# DSR-0609-ES8218-0410.net
KiCad netlist of a schematic drawn in Altium Designer
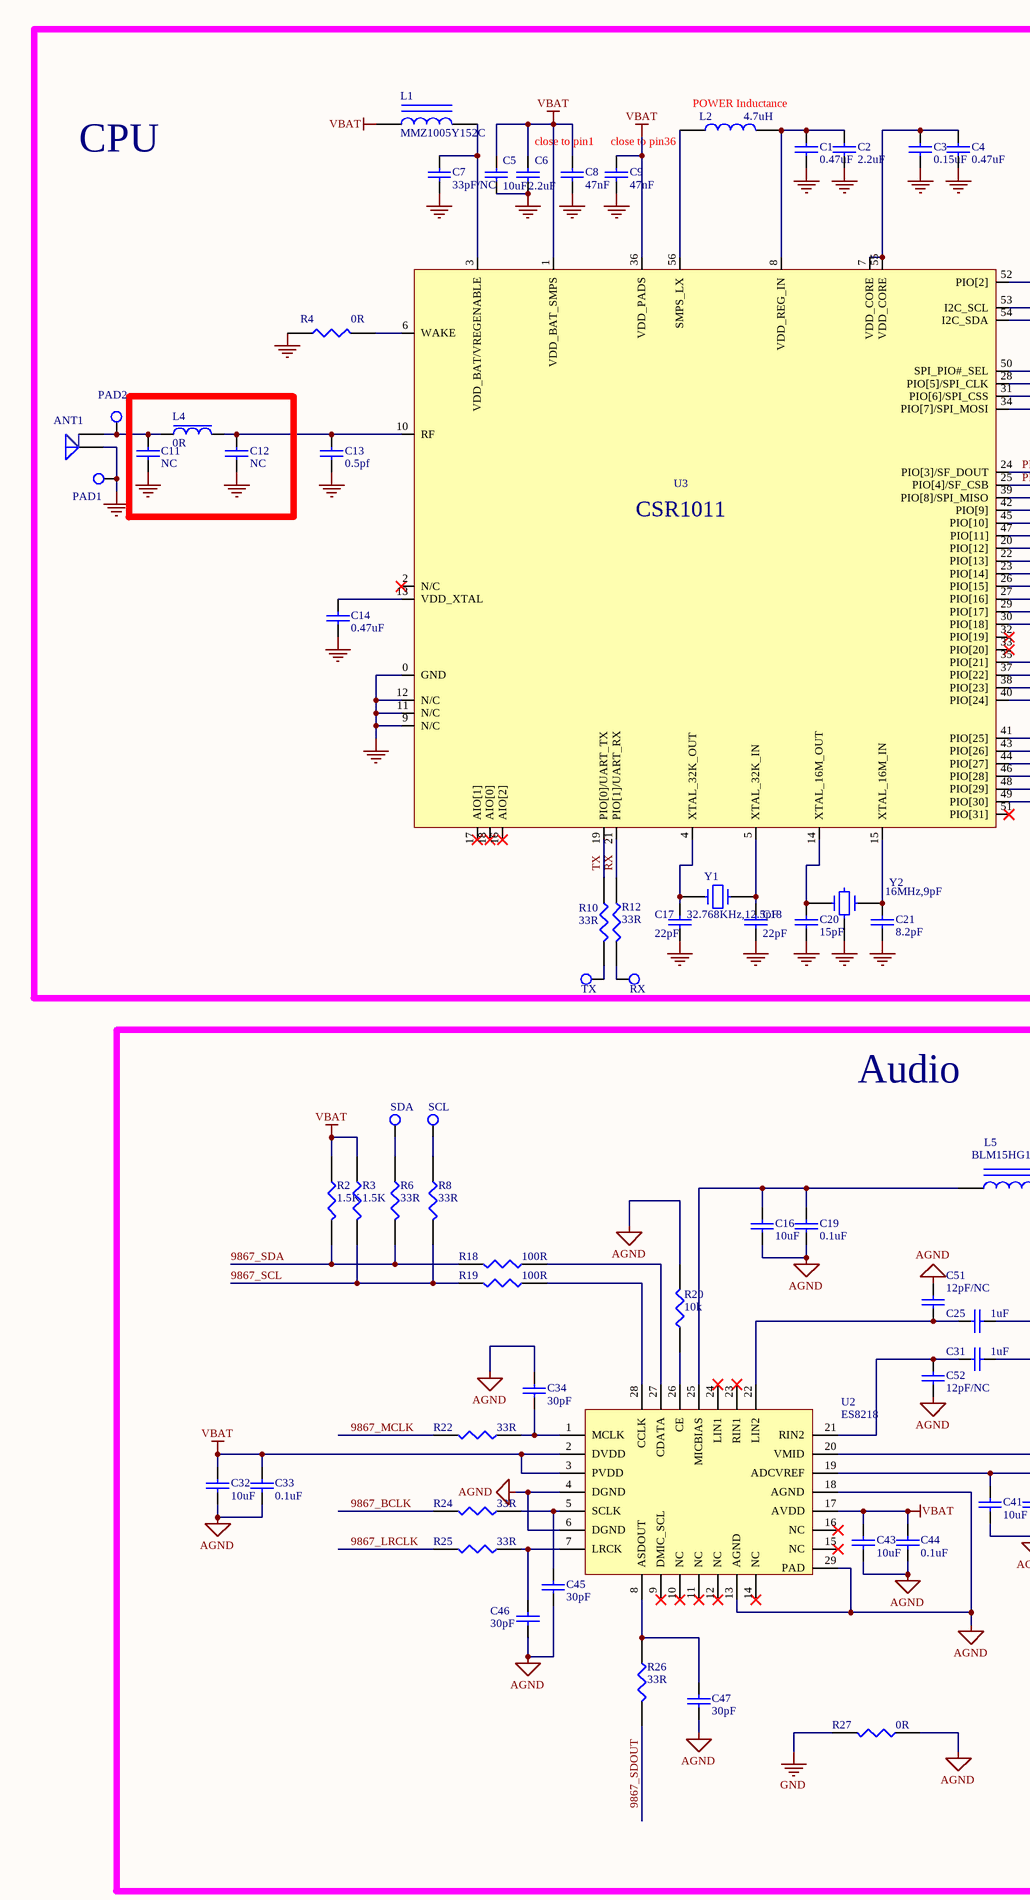
[diagram p0: DSR-0609-ES8218-0410.SchDoc, left]
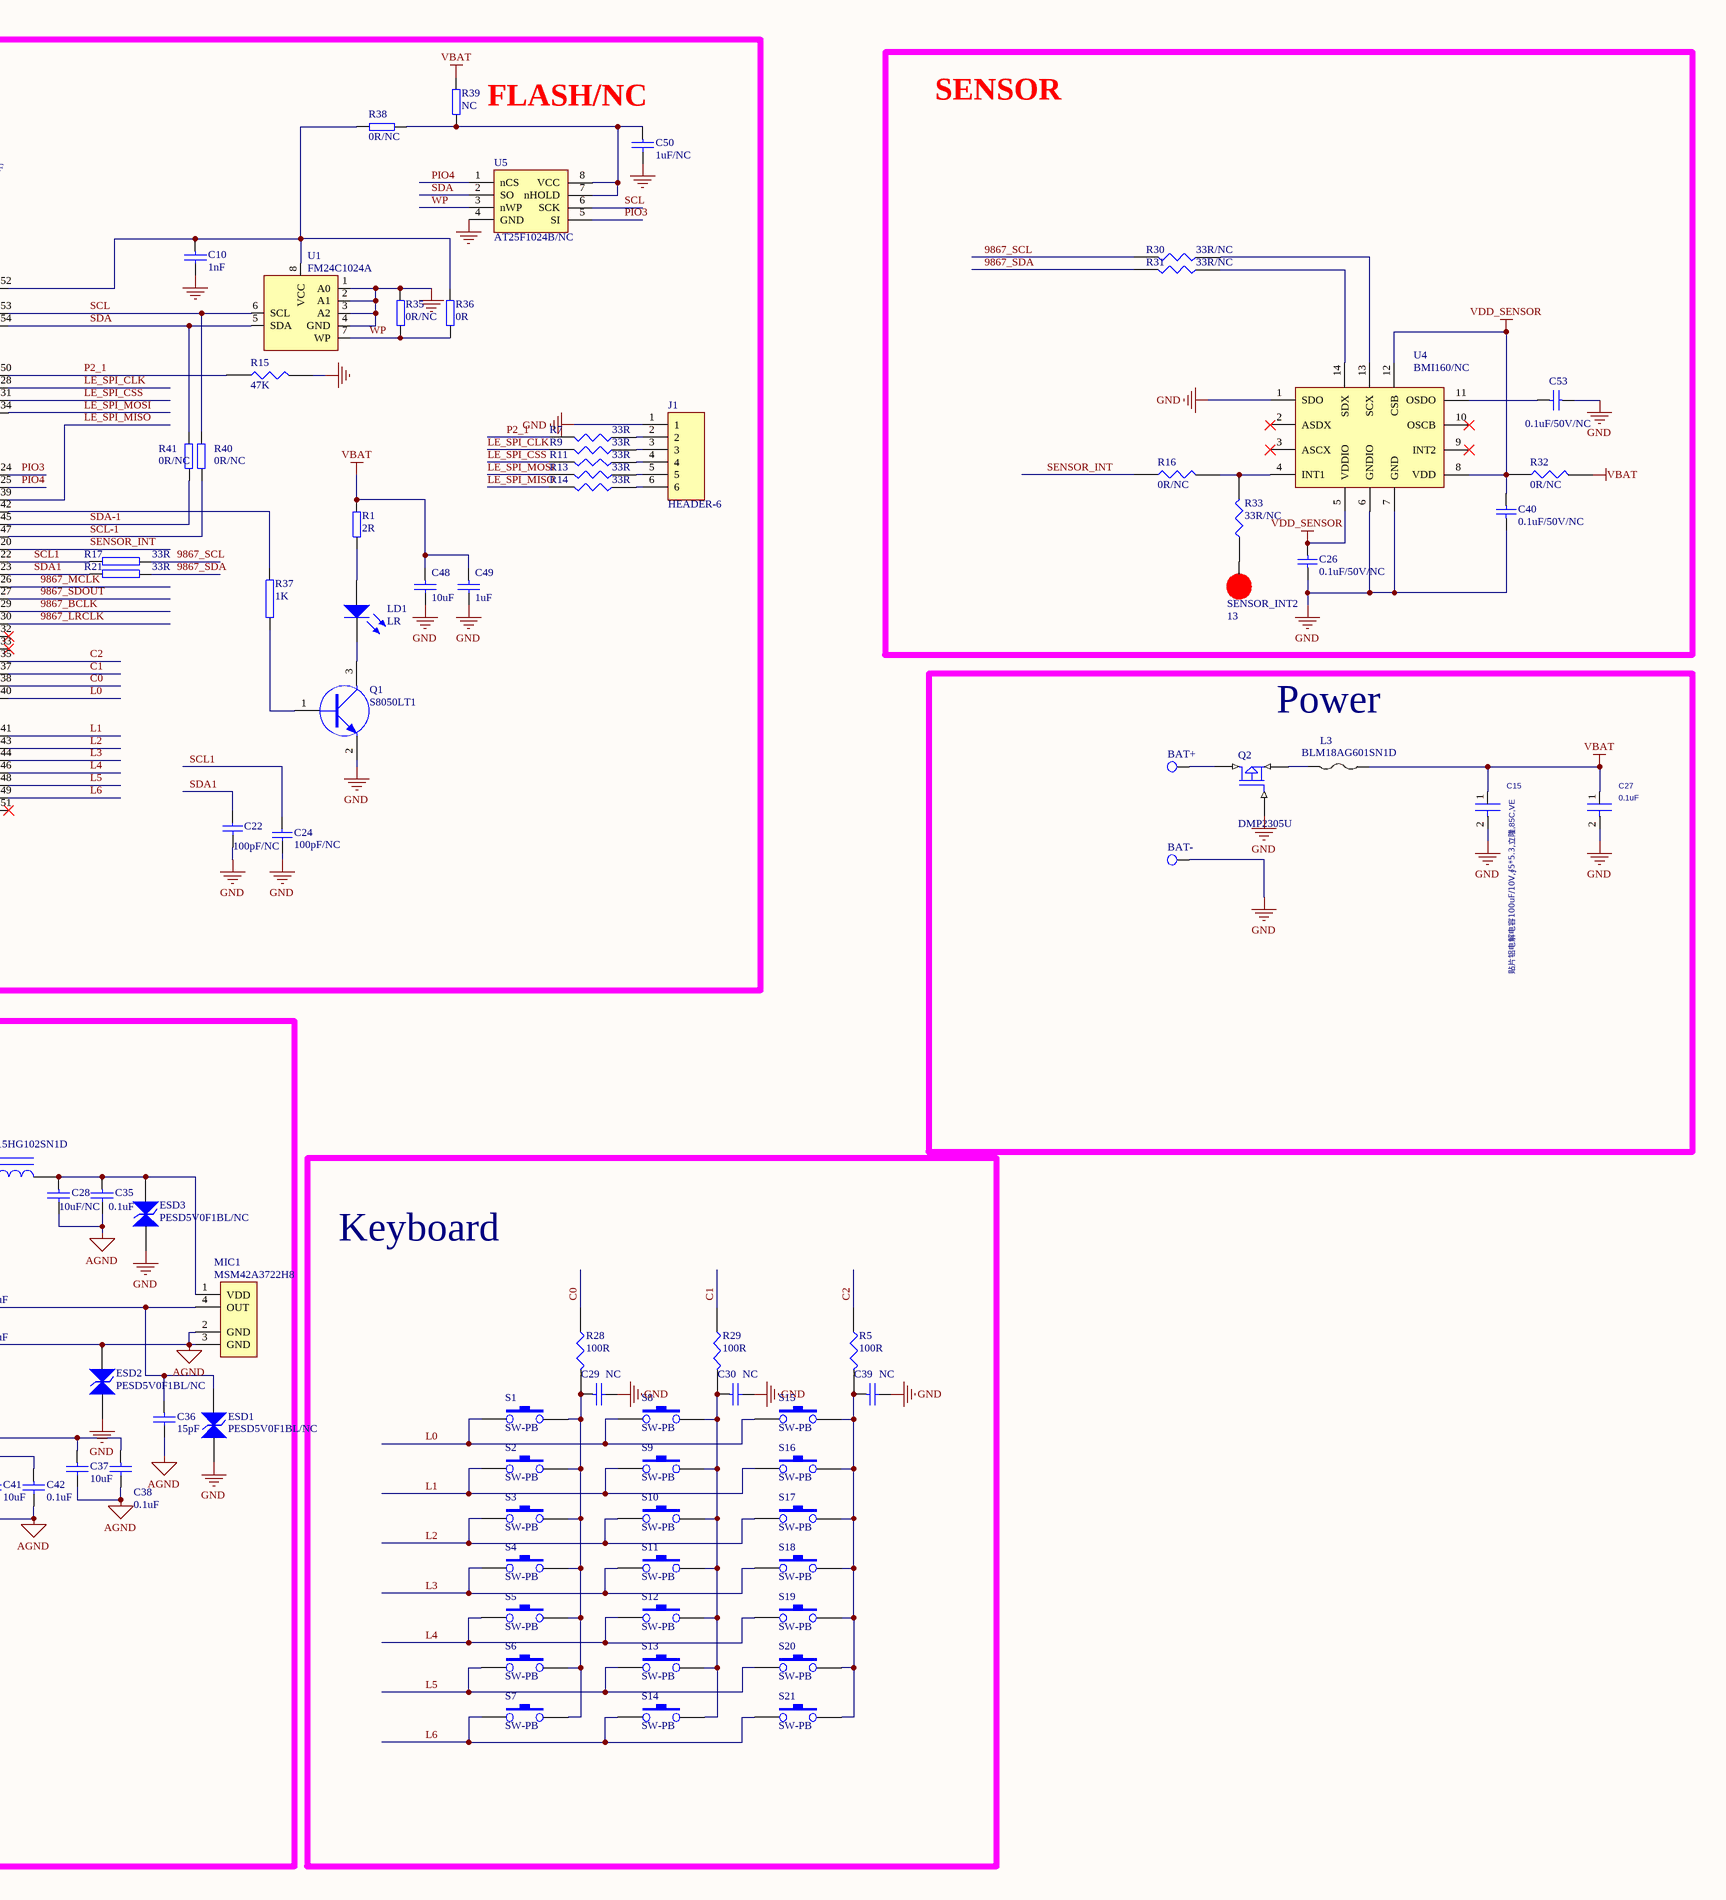
[diagram p1: DSR-0609-ES8218-0410.SchDoc, right]

(export (version "E")
  (design (tool "Eeschema 10.0.6"))
  (components
    (comp (ref "ANT1")
      (value "ANTENNA")
      (footprint "ACA-2012-A1-CC-S")
      (libsource (lib "dusun01-SCH") (part "ANTENNA"))
    )
    (comp (ref "BAT+") (value "TAP") (footprint "BAT") (libsource (lib "*") (part "TAP")))
    (comp (ref "BAT-") (value "TAP") (footprint "BAT") (libsource (lib "*") (part "TAP")))
    (comp (ref "C1")
      (value "0.47uF")
      (footprint "dusun01-pcb:C-0402")
      (description "Capacitor")
      (libsource (lib "*") (part "CAP"))
    )
    (comp (ref "C2")
      (value "2.2uF")
      (footprint "dusun01-pcb:C-0402")
      (description "Capacitor")
      (libsource (lib "*") (part "CAP"))
    )
    (comp (ref "C3")
      (value "0.15uF")
      (footprint "dusun01-pcb:C-0402")
      (description "Capacitor")
      (libsource (lib "*") (part "CAP"))
    )
    (comp (ref "C4")
      (value "0.47uF")
      (footprint "dusun01-pcb:C-0402")
      (description "Capacitor")
      (libsource (lib "*") (part "CAP"))
    )
    (comp (ref "C5")
      (value "10uF")
      (footprint "dusun01-pcb:C-0603")
      (description "Capacitor")
      (libsource (lib "*") (part "CAP"))
    )
    (comp (ref "C6")
      (value "2.2uF")
      (footprint "dusun01-pcb:C-0402")
      (description "Capacitor")
      (libsource (lib "*") (part "CAP"))
    )
    (comp (ref "C7")
      (value "33pF/NC")
      (footprint "dusun01-pcb:C-0402")
      (description "Capacitor")
      (libsource (lib "*") (part "CAP"))
    )
    (comp (ref "C8")
      (value "47nF")
      (footprint "dusun01-pcb:C-0402")
      (description "Capacitor")
      (libsource (lib "*") (part "CAP"))
    )
    (comp (ref "C9")
      (value "47nF")
      (footprint "dusun01-pcb:C-0402")
      (description "Capacitor")
      (libsource (lib "*") (part "CAP"))
    )
    (comp (ref "C10")
      (value "1nF")
      (footprint "dusun01-pcb:C-0402")
      (description "Capacitor")
      (libsource (lib "*") (part "CAP"))
    )
    (comp (ref "C11")
      (value "NC")
      (footprint "dusun01-pcb:C-0402")
      (description "Capacitor")
      (libsource (lib "*") (part "CAP"))
    )
    (comp (ref "C12")
      (value "NC")
      (footprint "dusun01-pcb:C-0402")
      (description "Capacitor")
      (libsource (lib "*") (part "CAP"))
    )
    (comp (ref "C13")
      (value "0.5pf")
      (footprint "dusun01-pcb:C-0402")
      (description "Capacitor")
      (libsource (lib "*") (part "CAP"))
    )
    (comp (ref "C14")
      (value "0.47uF")
      (footprint "dusun01-pcb:C-0402")
      (description "Capacitor")
      (libsource (lib "*") (part "CAP"))
    )
    (comp (ref "C15")
      (value "贴片铝电解电容100uF/10V,∮5*5.3,立隆,85C,VE")
      (footprint "dusun02-pcb:CAP_ALUM-C")
      (libsource (lib "*") (part "C_Dup1"))
    )
    (comp (ref "C16")
      (value "10uF")
      (footprint "dusun01-pcb:C-0603")
      (description "Capacitor")
      (libsource (lib "*") (part "CAP"))
    )
    (comp (ref "C17")
      (value "22pF")
      (footprint "dusun01-pcb:C-0402")
      (description "Capacitor")
      (libsource (lib "*") (part "CAP"))
    )
    (comp (ref "C18")
      (value "22pF")
      (footprint "dusun01-pcb:C-0402")
      (description "Capacitor")
      (libsource (lib "*") (part "CAP"))
    )
    (comp (ref "C19")
      (value "0.1uF")
      (footprint "C-0402")
      (description "Capacitor")
      (libsource (lib "*") (part "CAP"))
    )
    (comp (ref "C20")
      (value "15pF")
      (footprint "dusun01-pcb:C-0402")
      (description "Capacitor")
      (libsource (lib "*") (part "CAP"))
    )
    (comp (ref "C21")
      (value "8.2pF")
      (footprint "dusun01-pcb:C-0402")
      (description "Capacitor")
      (libsource (lib "*") (part "CAP"))
    )
    (comp (ref "C22") (value "100pF/NC") (footprint "dusun01-pcb:C-0402") (libsource (lib "") (part "CAP_1")))
    (comp (ref "C24") (value "100pF/NC") (footprint "dusun01-pcb:C-0402") (libsource (lib "") (part "CAP_1")))
    (comp (ref "C25")
      (value "1uF")
      (footprint "C-0402")
      (description "Capacitor")
      (libsource (lib "*") (part "CAP"))
    )
    (comp (ref "C26")
      (value "0.1uF/50V/NC")
      (footprint "C-0402")
      (description "capacitor 27 pF NPO , +/- 2 %, SMD case 0603")
      (fields
        (field (name "MANUFACTURER") "Generic Components")
        (field (name "PUBLISHER") "Altium Hobart Technology Centre")
      )
      (libsource (lib "Miscellaneous Devices") (part "Cap"))
    )
    (comp (ref "C27") (value "0.1uF") (footprint "C-0603") (libsource (lib "*") (part "C_Dup1")))
    (comp (ref "C28")
      (value "10uF/NC")
      (footprint "dusun01-pcb:C-0603")
      (description "Capacitor")
      (libsource (lib "*") (part "CAP"))
    )
    (comp (ref "C29")
      (value "NC")
      (footprint "C-0402")
      (description "Capacitor")
      (libsource (lib "*") (part "CAP"))
    )
    (comp (ref "C30")
      (value "NC")
      (footprint "C-0402")
      (description "Capacitor")
      (libsource (lib "*") (part "CAP"))
    )
    (comp (ref "C31")
      (value "1uF")
      (footprint "C-0402")
      (description "Capacitor")
      (libsource (lib "*") (part "CAP"))
    )
    (comp (ref "C32")
      (value "10uF")
      (footprint "dusun01-pcb:C-0603")
      (description "Capacitor")
      (libsource (lib "*") (part "CAP"))
    )
    (comp (ref "C33")
      (value "0.1uF")
      (footprint "C-0402")
      (description "Capacitor")
      (libsource (lib "*") (part "CAP"))
    )
    (comp (ref "C34")
      (value "30pF")
      (footprint "C-0402")
      (description "Capacitor")
      (libsource (lib "*") (part "CAP"))
    )
    (comp (ref "C35")
      (value "0.1uF")
      (footprint "C-0402")
      (description "Capacitor")
      (libsource (lib "*") (part "CAP"))
    )
    (comp (ref "C36")
      (value "15pF")
      (footprint "dusun01-pcb:C-0402")
      (description "Capacitor")
      (libsource (lib "*") (part "CAP"))
    )
    (comp (ref "C37")
      (value "10uF")
      (footprint "dusun01-pcb:C-0603")
      (description "Capacitor")
      (libsource (lib "*") (part "CAP"))
    )
    (comp (ref "C38")
      (value "0.1uF")
      (footprint "C-0402")
      (description "Capacitor")
      (libsource (lib "*") (part "CAP"))
    )
    (comp (ref "C39")
      (value "NC")
      (footprint "C-0402")
      (description "Capacitor")
      (libsource (lib "*") (part "CAP"))
    )
    (comp (ref "C40")
      (value "0.1uF/50V/NC")
      (footprint "C-0402")
      (description "capacitor 27 pF NPO , +/- 2 %, SMD case 0603")
      (fields
        (field (name "MANUFACTURER") "Generic Components")
        (field (name "PUBLISHER") "Altium Hobart Technology Centre")
      )
      (libsource (lib "Miscellaneous Devices") (part "Cap"))
    )
    (comp (ref "C41")
      (value "10uF")
      (footprint "dusun01-pcb:C-0603")
      (description "Capacitor")
      (libsource (lib "*") (part "CAP"))
    )
    (comp (ref "C42")
      (value "0.1uF")
      (footprint "C-0402")
      (description "Capacitor")
      (libsource (lib "*") (part "CAP"))
    )
    (comp (ref "C43")
      (value "10uF")
      (footprint "dusun01-pcb:C-0603")
      (description "Capacitor")
      (libsource (lib "*") (part "CAP"))
    )
    (comp (ref "C44")
      (value "0.1uF")
      (footprint "C-0402")
      (description "Capacitor")
      (libsource (lib "*") (part "CAP"))
    )
    (comp (ref "C45")
      (value "30pF")
      (footprint "C-0402")
      (description "Capacitor")
      (libsource (lib "*") (part "CAP"))
    )
    (comp (ref "C46")
      (value "30pF")
      (footprint "C-0402")
      (description "Capacitor")
      (libsource (lib "*") (part "CAP"))
    )
    (comp (ref "C47")
      (value "30pF")
      (footprint "C-0402")
      (description "Capacitor")
      (libsource (lib "*") (part "CAP"))
    )
    (comp (ref "C48")
      (value "10uF")
      (footprint "dusun01-pcb:C-0603")
      (description "Capacitor")
      (libsource (lib "*") (part "CAP"))
    )
    (comp (ref "C49")
      (value "1uF")
      (footprint "dusun01-pcb:C-0603")
      (description "Capacitor")
      (libsource (lib "*") (part "CAP"))
    )
    (comp (ref "C50")
      (value "1uF/NC")
      (footprint "C-0402")
      (description "Capacitor")
      (libsource (lib "") (part "CAP_2"))
    )
    (comp (ref "C51")
      (value "12pF/NC")
      (footprint "dusun01-pcb:C-0402")
      (description "Capacitor")
      (libsource (lib "*") (part "CAP"))
    )
    (comp (ref "C52")
      (value "12pF/NC")
      (footprint "dusun01-pcb:C-0402")
      (description "Capacitor")
      (libsource (lib "*") (part "CAP"))
    )
    (comp (ref "C53")
      (value "0.1uF/50V/NC")
      (footprint "C-0402")
      (description "capacitor 27 pF NPO , +/- 2 %, SMD case 0603")
      (fields
        (field (name "MANUFACTURER") "Generic Components")
        (field (name "PUBLISHER") "Altium Hobart Technology Centre")
      )
      (libsource (lib "Miscellaneous Devices") (part "Cap"))
    )
    (comp (ref "ESD1")
      (value "PESD5V0F1BL/NC")
      (footprint "dusun02-pcb:SOD882")
      (libsource (lib "dusun02-SCH") (part "ESD"))
    )
    (comp (ref "ESD2")
      (value "PESD5V0F1BL/NC")
      (footprint "dusun02-pcb:SOD882")
      (libsource (lib "dusun02-SCH") (part "ESD"))
    )
    (comp (ref "ESD3")
      (value "PESD5V0F1BL/NC")
      (footprint "dusun02-pcb:SOD882")
      (libsource (lib "dusun02-SCH") (part "ESD"))
    )
    (comp (ref "J1")
      (value "HEADER-6")
      (footprint "PH-1*6-2.0")
      (libsource (lib "dusun01-SCH") (part "HEADER-6"))
    )
    (comp (ref "L1") (value "MMZ1005Y152C") (footprint "R-0402") (libsource (lib "*") (part "INDUCTOR IRON")))
    (comp (ref "L2") (value "4.7uH") (footprint "R-1008") (libsource (lib "*") (part "INDUCTOR")))
    (comp (ref "L3")
      (value "BLM18AG601SN1D")
      (footprint "dusun01-pcb:R-0603")
      (libsource (lib "*") (part "Inductance"))
    )
    (comp (ref "L4") (value "0R") (footprint "R-0402") (libsource (lib "dusun01-SCH") (part "INDUCTOR")))
    (comp (ref "L5")
      (value "BLM15HG102SN1D")
      (footprint "R-0402")
      (libsource (lib "*") (part "INDUCTOR IRON"))
    )
    (comp (ref "LD1")
      (value "LR")
      (footprint "dusun01-pcb:IR-4.2-3")
      (libsource (lib "dusun01-SCH") (part "LED"))
    )
    (comp (ref "MIC1")
      (value "MSM42A3722H8")
      (footprint "dusun02-pcb:MSM42A3722H8")
      (libsource (lib "dusun02-SCH") (part "MSM42A3722H8"))
    )
    (comp (ref "PAD1")
      (value "TAP")
      (footprint "dusun01-pcb:TS-1.0")
      (libsource (lib "dusun02-SCH") (part "TAP"))
    )
    (comp (ref "PAD2")
      (value "TAP")
      (footprint "dusun01-pcb:TS-1.0")
      (libsource (lib "dusun02-SCH") (part "TAP"))
    )
    (comp (ref "Q1")
      (value "S8050LT1")
      (footprint "SOT-23")
      (description "NPN型晶体管")
      (libsource (lib "dusun01-SCH") (part "NPN"))
    )
    (comp (ref "Q2")
      (value "DMP2305U")
      (footprint "SOT-23")
      (libsource (lib "dusun02-SCH") (part "MOSFET P"))
    )
    (comp (ref "R1") (value "2R") (footprint "R-0805") (libsource (lib "dusun01-SCH") (part "RES")))
    (comp (ref "R2") (value "1.5K") (footprint "dusun01-pcb:R-0402") (libsource (lib "*") (part "RES1")))
    (comp (ref "R3") (value "1.5K") (footprint "dusun01-pcb:R-0402") (libsource (lib "*") (part "RES1")))
    (comp (ref "R4") (value "0R") (footprint "R-0402") (libsource (lib "*") (part "RES1")))
    (comp (ref "R5") (value "100R") (footprint "dusun01-pcb:R-0402") (libsource (lib "*") (part "RES1")))
    (comp (ref "R6") (value "33R") (footprint "dusun01-pcb:R-0402") (libsource (lib "*") (part "RES1")))
    (comp (ref "R7") (value "33R") (footprint "dusun01-pcb:R-0402") (libsource (lib "*") (part "RES1")))
    (comp (ref "R8") (value "33R") (footprint "dusun01-pcb:R-0402") (libsource (lib "*") (part "RES1")))
    (comp (ref "R9") (value "33R") (footprint "dusun01-pcb:R-0402") (libsource (lib "*") (part "RES1")))
    (comp (ref "R10") (value "33R") (footprint "dusun01-pcb:R-0402") (libsource (lib "*") (part "RES1")))
    (comp (ref "R11") (value "33R") (footprint "dusun01-pcb:R-0402") (libsource (lib "*") (part "RES1")))
    (comp (ref "R12") (value "33R") (footprint "dusun01-pcb:R-0402") (libsource (lib "*") (part "RES1")))
    (comp (ref "R13") (value "33R") (footprint "dusun01-pcb:R-0402") (libsource (lib "*") (part "RES1")))
    (comp (ref "R14") (value "33R") (footprint "dusun01-pcb:R-0402") (libsource (lib "*") (part "RES1")))
    (comp (ref "R15") (value "47K") (footprint "dusun01-pcb:R-0402") (libsource (lib "*") (part "RES1")))
    (comp (ref "R16") (value "0R/NC") (footprint "R-0402") (libsource (lib "*") (part "RES1")))
    (comp (ref "R17") (value "33R") (footprint "R-0402") (libsource (lib "") (part "RES_1")))
    (comp (ref "R18") (value "100R") (footprint "dusun01-pcb:R-0402") (libsource (lib "*") (part "RES1")))
    (comp (ref "R19") (value "100R") (footprint "dusun01-pcb:R-0402") (libsource (lib "*") (part "RES1")))
    (comp (ref "R20") (value "10k") (footprint "R-0402") (libsource (lib "*") (part "RES1")))
    (comp (ref "R21") (value "33R") (footprint "R-0402") (libsource (lib "") (part "RES_1")))
    (comp (ref "R22") (value "33R") (footprint "dusun01-pcb:R-0402") (libsource (lib "*") (part "RES1")))
    (comp (ref "R24") (value "33R") (footprint "dusun01-pcb:R-0402") (libsource (lib "*") (part "RES1")))
    (comp (ref "R25") (value "33R") (footprint "dusun01-pcb:R-0402") (libsource (lib "*") (part "RES1")))
    (comp (ref "R26") (value "33R") (footprint "dusun01-pcb:R-0402") (libsource (lib "*") (part "RES1")))
    (comp (ref "R27") (value "0R") (footprint "dusun02-pcb:R-0603") (libsource (lib "*") (part "RES1")))
    (comp (ref "R28") (value "100R") (footprint "dusun01-pcb:R-0402") (libsource (lib "*") (part "RES1")))
    (comp (ref "R29") (value "100R") (footprint "dusun01-pcb:R-0402") (libsource (lib "*") (part "RES1")))
    (comp (ref "R30") (value "33R/NC") (footprint "R-0402") (libsource (lib "*") (part "RES1")))
    (comp (ref "R31") (value "33R/NC") (footprint "R-0402") (libsource (lib "*") (part "RES1")))
    (comp (ref "R32") (value "0R/NC") (footprint "R-0402") (libsource (lib "*") (part "RES1")))
    (comp (ref "R33") (value "33R/NC") (footprint "R-0402") (libsource (lib "*") (part "RES1")))
    (comp (ref "R35") (value "0R/NC") (footprint "R-0402") (libsource (lib "dusun01-SCH") (part "RES")))
    (comp (ref "R36") (value "0R") (footprint "R-0402") (libsource (lib "dusun01-SCH") (part "RES")))
    (comp (ref "R37") (value "1K") (footprint "R-0402") (libsource (lib "") (part "RES_2")))
    (comp (ref "R38") (value "0R/NC") (footprint "R-0402") (libsource (lib "dusun02-SCH") (part "RES")))
    (comp (ref "R39") (value "NC") (footprint "R-0402") (libsource (lib "dusun02-SCH") (part "RES")))
    (comp (ref "R40") (value "0R/NC") (footprint "R-0402") (libsource (lib "dusun02-SCH") (part "RES")))
    (comp (ref "R41") (value "0R/NC") (footprint "R-0402") (libsource (lib "dusun02-SCH") (part "RES")))
    (comp (ref "RX") (value "TAP") (footprint "TS-1.0") (libsource (lib "dusun01-SCH") (part "TAP")))
    (comp (ref "S1") (value "SW-PB") (footprint "K mat D5") (libsource (lib "dusun") (part "SW-PB")))
    (comp (ref "S2") (value "SW-PB") (footprint "K mat D5") (libsource (lib "dusun01-SCH") (part "SW-PB")))
    (comp (ref "S3") (value "SW-PB") (footprint "K mat D5") (libsource (lib "dusun") (part "SW-PB")))
    (comp (ref "S4") (value "SW-PB") (footprint "K mat D5") (libsource (lib "dusun") (part "SW-PB")))
    (comp (ref "S5") (value "SW-PB") (footprint "K mat D5") (libsource (lib "dusun") (part "SW-PB")))
    (comp (ref "S6") (value "SW-PB") (footprint "K mat D5") (libsource (lib "dusun") (part "SW-PB")))
    (comp (ref "S7") (value "SW-PB") (footprint "K mat D5") (libsource (lib "dusun") (part "SW-PB")))
    (comp (ref "S8") (value "SW-PB") (footprint "K mat D5") (libsource (lib "dusun") (part "SW-PB")))
    (comp (ref "S9") (value "SW-PB") (footprint "K mat D5") (libsource (lib "dusun") (part "SW-PB")))
    (comp (ref "S10") (value "SW-PB") (footprint "K mat D5") (libsource (lib "dusun") (part "SW-PB")))
    (comp (ref "S11") (value "SW-PB") (footprint "K mat D5") (libsource (lib "dusun") (part "SW-PB")))
    (comp (ref "S12") (value "SW-PB") (footprint "K mat D5") (libsource (lib "dusun01-SCH") (part "SW-PB")))
    (comp (ref "S13") (value "SW-PB") (footprint "K mat D5") (libsource (lib "dusun") (part "SW-PB")))
    (comp (ref "S14") (value "SW-PB") (footprint "K mat D5") (libsource (lib "dusun01-SCH") (part "SW-PB")))
    (comp (ref "S15")
      (value "SW-PB")
      (footprint "KG4.5*4.5-SMD-1")
      (libsource (lib "dusun01-SCH") (part "SW-PB"))
    )
    (comp (ref "S16") (value "SW-PB") (footprint "K mat D5") (libsource (lib "dusun01-SCH") (part "SW-PB")))
    (comp (ref "S17") (value "SW-PB") (footprint "K mat D5") (libsource (lib "dusun01-SCH") (part "SW-PB")))
    (comp (ref "S18") (value "SW-PB") (footprint "K mat D5") (libsource (lib "dusun01-SCH") (part "SW-PB")))
    (comp (ref "S19") (value "SW-PB") (footprint "K mat D5") (libsource (lib "dusun01-SCH") (part "SW-PB")))
    (comp (ref "S20") (value "SW-PB") (footprint "K mat D5") (libsource (lib "dusun01-SCH") (part "SW-PB")))
    (comp (ref "S21") (value "SW-PB") (footprint "K mat D5") (libsource (lib "dusun01-SCH") (part "SW-PB")))
    (comp (ref "SCL") (value "TAP") (footprint "TS-1.0") (libsource (lib "dusun01-SCH") (part "TAP")))
    (comp (ref "SDA") (value "TAP") (footprint "TS-1.0") (libsource (lib "dusun01-SCH") (part "TAP")))
    (comp (ref "SENSOR_INT2") (value "13") (footprint "TS-1.0") (libsource (lib "*") (part "TESTPOINT")))
    (comp (ref "TX") (value "TAP") (footprint "TS-1.0") (libsource (lib "dusun01-SCH") (part "TAP")))
    (comp (ref "U1")
      (value "FM24C1024A")
      (footprint "dusun01-pcb:SOP08-6.0-1.27")
      (libsource (lib "*") (part "AT24C512"))
    )
    (comp (ref "U2") (value "ES8218") (libsource (lib "dusun01-SCH") (part "ES8218")))
    (comp (ref "U3") (value "CSR1011") (footprint "QFN-56-8*8") (libsource (lib "*") (part "CSR1001")))
    (comp (ref "U4")
      (value "BMI160/NC")
      (footprint "dusun01-pcb:LGA-14")
      (libsource (lib "dusun01-SCH") (part "BMI160"))
    )
    (comp (ref "U5")
      (value "AT25F1024B/NC")
      (footprint "dusun01-pcb:SOP08-6.0-1.27")
      (libsource (lib "dusun02-SCH") (part "AT25F512B"))
    )
    (comp (ref "Y1")
      (value "32.768KHz,12.5pF")
      (footprint "32.768Khz-3215")
      (libsource (lib "dusun01-SCH") (part "CRYSTAL2"))
    )
    (comp (ref "Y2")
      (value "16MHz,9pF")
      (footprint "XD3225-1-12M-125M")
      (libsource (lib "dusun01-SCH") (part "CRYSTAL4"))
    )
  )
  (nets
    (net (code "1") (name "/9867_BCLK") (class "Default")
      (node (ref "R24") (pin "2") (pinfunction "2_2") (pintype "passive"))
      (node (ref "U3") (pin "29") (pinfunction "PIO[17]_29") (pintype "passive"))
    )
    (net (code "2") (name "/9867_LRCLK") (class "Default")
      (node (ref "R25") (pin "2") (pinfunction "2_2") (pintype "passive"))
      (node (ref "U3") (pin "30") (pinfunction "PIO[18]_30") (pintype "passive"))
    )
    (net (code "3") (name "/9867_MCLK") (class "Default")
      (node (ref "R22") (pin "2") (pinfunction "2_2") (pintype "passive"))
      (node (ref "U3") (pin "26") (pinfunction "PIO[15]_26") (pintype "passive"))
    )
    (net (code "4") (name "/9867_SCL") (class "Default")
      (node (ref "R17") (pin "1") (pinfunction "1_1") (pintype "passive"))
      (node (ref "R19") (pin "2") (pinfunction "2_2") (pintype "passive"))
      (node (ref "R3") (pin "2") (pinfunction "2_2") (pintype "passive"))
      (node (ref "R30") (pin "2") (pinfunction "2_2") (pintype "passive"))
      (node (ref "R8") (pin "2") (pinfunction "2_2") (pintype "passive"))
    )
    (net (code "5") (name "/9867_SDA") (class "Default")
      (node (ref "R18") (pin "2") (pinfunction "2_2") (pintype "passive"))
      (node (ref "R2") (pin "2") (pinfunction "2_2") (pintype "passive"))
      (node (ref "R21") (pin "1") (pinfunction "1_1") (pintype "passive"))
      (node (ref "R31") (pin "2") (pinfunction "2_2") (pintype "passive"))
      (node (ref "R6") (pin "2") (pinfunction "2_2") (pintype "passive"))
    )
    (net (code "6") (name "/9867_SDOUT") (class "Default")
      (node (ref "R26") (pin "2") (pinfunction "2_2") (pintype "passive"))
      (node (ref "U3") (pin "27") (pinfunction "PIO[16]_27") (pintype "passive"))
    )
    (net (code "7") (name "/C0") (class "Default")
      (node (ref "R28") (pin "1") (pinfunction "1_1") (pintype "passive"))
      (node (ref "U3") (pin "38") (pinfunction "PIO[23]_38") (pintype "passive"))
    )
    (net (code "8") (name "/C1") (class "Default")
      (node (ref "R29") (pin "1") (pinfunction "1_1") (pintype "passive"))
      (node (ref "U3") (pin "37") (pinfunction "PIO[22]_37") (pintype "passive"))
    )
    (net (code "9") (name "/C2") (class "Default")
      (node (ref "R5") (pin "1") (pinfunction "1_1") (pintype "passive"))
      (node (ref "U3") (pin "35") (pinfunction "PIO[21]_35") (pintype "passive"))
    )
    (net (code "10") (name "/L0") (class "Default")
      (node (ref "S1") (pin "1") (pinfunction "1_1") (pintype "passive"))
      (node (ref "S15") (pin "1") (pinfunction "1_1") (pintype "passive"))
      (node (ref "S8") (pin "1") (pinfunction "1_1") (pintype "passive"))
      (node (ref "U3") (pin "40") (pinfunction "PIO[24]_40") (pintype "passive"))
    )
    (net (code "11") (name "/L1") (class "Default")
      (node (ref "S16") (pin "1") (pinfunction "1_1") (pintype "passive"))
      (node (ref "S2") (pin "1") (pinfunction "1_1") (pintype "passive"))
      (node (ref "S9") (pin "1") (pinfunction "1_1") (pintype "passive"))
      (node (ref "U3") (pin "41") (pinfunction "PIO[25]_41") (pintype "passive"))
    )
    (net (code "12") (name "/L2") (class "Default")
      (node (ref "S10") (pin "1") (pinfunction "1_1") (pintype "passive"))
      (node (ref "S17") (pin "1") (pinfunction "1_1") (pintype "passive"))
      (node (ref "S3") (pin "1") (pinfunction "1_1") (pintype "passive"))
      (node (ref "U3") (pin "43") (pinfunction "PIO[26]_43") (pintype "passive"))
    )
    (net (code "13") (name "/L3") (class "Default")
      (node (ref "S11") (pin "1") (pinfunction "1_1") (pintype "passive"))
      (node (ref "S18") (pin "1") (pinfunction "1_1") (pintype "passive"))
      (node (ref "S4") (pin "1") (pinfunction "1_1") (pintype "passive"))
      (node (ref "U3") (pin "44") (pinfunction "PIO[27]_44") (pintype "passive"))
    )
    (net (code "14") (name "/L4") (class "Default")
      (node (ref "S12") (pin "1") (pinfunction "1_1") (pintype "passive"))
      (node (ref "S19") (pin "1") (pinfunction "1_1") (pintype "passive"))
      (node (ref "S5") (pin "1") (pinfunction "1_1") (pintype "passive"))
      (node (ref "U3") (pin "46") (pinfunction "PIO[28]_46") (pintype "passive"))
    )
    (net (code "15") (name "/L5") (class "Default")
      (node (ref "S13") (pin "1") (pinfunction "1_1") (pintype "passive"))
      (node (ref "S20") (pin "1") (pinfunction "1_1") (pintype "passive"))
      (node (ref "S6") (pin "1") (pinfunction "1_1") (pintype "passive"))
      (node (ref "U3") (pin "48") (pinfunction "PIO[29]_48") (pintype "passive"))
    )
    (net (code "16") (name "/L6") (class "Default")
      (node (ref "S14") (pin "1") (pinfunction "1_1") (pintype "passive"))
      (node (ref "S21") (pin "1") (pinfunction "1_1") (pintype "passive"))
      (node (ref "S7") (pin "1") (pinfunction "1_1") (pintype "passive"))
      (node (ref "U3") (pin "49") (pinfunction "PIO[30]_49") (pintype "passive"))
    )
    (net (code "17") (name "/LE_SPI_CLK") (class "Default")
      (node (ref "R9") (pin "2") (pinfunction "2_2") (pintype "passive"))
      (node (ref "U3") (pin "28") (pinfunction "PIO[5]/SPI_CLK_28") (pintype "passive"))
    )
    (net (code "18") (name "/LE_SPI_CSS") (class "Default")
      (node (ref "R11") (pin "2") (pinfunction "2_2") (pintype "passive"))
      (node (ref "U3") (pin "31") (pinfunction "PIO[6]/SPI_CSS_31") (pintype "passive"))
    )
    (net (code "19") (name "/LE_SPI_MISO") (class "Default")
      (node (ref "R14") (pin "2") (pinfunction "2_2") (pintype "passive"))
      (node (ref "U3") (pin "39") (pinfunction "PIO[8]/SPI_MISO_39") (pintype "passive"))
    )
    (net (code "20") (name "/LE_SPI_MOSI") (class "Default")
      (node (ref "R13") (pin "2") (pinfunction "2_2") (pintype "passive"))
      (node (ref "U3") (pin "34") (pinfunction "PIO[7]/SPI_MOSI_34") (pintype "passive"))
    )
    (net (code "21") (name "/P2_1") (class "Default")
      (node (ref "R15") (pin "1") (pinfunction "1_1") (pintype "passive"))
      (node (ref "R7") (pin "2") (pinfunction "2_2") (pintype "passive"))
      (node (ref "U3") (pin "50") (pinfunction "SPI_PIO#_SEL_50") (pintype "passive"))
    )
    (net (code "22") (name "/PIO3") (class "Default")
      (node (ref "U3") (pin "24") (pinfunction "PIO[3]/SF_DOUT_24") (pintype "passive"))
      (node (ref "U5") (pin "5") (pinfunction "SI_5") (pintype "passive"))
    )
    (net (code "23") (name "/PIO4") (class "Default")
      (node (ref "U3") (pin "25") (pinfunction "PIO[4]/SF_CSB_25") (pintype "passive"))
      (node (ref "U5") (pin "1") (pinfunction "nCS_1") (pintype "passive"))
    )
    (net (code "24") (name "/RX") (class "Default")
      (node (ref "R12") (pin "1") (pinfunction "1_1") (pintype "passive"))
      (node (ref "U3") (pin "21") (pinfunction "PIO[1]/UART_RX_21") (pintype "passive"))
    )
    (net (code "25") (name "/SCL") (class "Default")
      (node (ref "R40") (pin "2") (pinfunction "2_2") (pintype "passive"))
      (node (ref "U1") (pin "6") (pinfunction "SCL_6") (pintype "passive"))
      (node (ref "U3") (pin "53") (pinfunction "I2C_SCL_53") (pintype "passive"))
      (node (ref "U5") (pin "6") (pinfunction "SCK_6") (pintype "passive"))
    )
    (net (code "26") (name "/SCL-1") (class "Default")
      (node (ref "R40") (pin "1") (pinfunction "1_1") (pintype "passive"))
      (node (ref "U3") (pin "47") (pinfunction "PIO[11]_47") (pintype "passive"))
    )
    (net (code "27") (name "/SCL1") (class "Default")
      (node (ref "C24") (pin "2") (pinfunction "2_2") (pintype "passive"))
      (node (ref "R17") (pin "2") (pinfunction "2_2") (pintype "passive"))
      (node (ref "U3") (pin "22") (pinfunction "PIO[13]_22") (pintype "passive"))
    )
    (net (code "28") (name "/SDA") (class "Default")
      (node (ref "R41") (pin "2") (pinfunction "2_2") (pintype "passive"))
      (node (ref "U1") (pin "5") (pinfunction "SDA_5") (pintype "passive"))
      (node (ref "U3") (pin "54") (pinfunction "I2C_SDA_54") (pintype "passive"))
      (node (ref "U5") (pin "2") (pinfunction "SO_2") (pintype "passive"))
    )
    (net (code "29") (name "/SDA-1") (class "Default")
      (node (ref "R41") (pin "1") (pinfunction "1_1") (pintype "passive"))
      (node (ref "U3") (pin "45") (pinfunction "PIO[10]_45") (pintype "passive"))
    )
    (net (code "30") (name "/SDA1") (class "Default")
      (node (ref "C22") (pin "2") (pinfunction "2_2") (pintype "passive"))
      (node (ref "R21") (pin "2") (pinfunction "2_2") (pintype "passive"))
      (node (ref "U3") (pin "23") (pinfunction "PIO[14]_23") (pintype "passive"))
    )
    (net (code "31") (name "/SENSOR_INT") (class "Default")
      (node (ref "R16") (pin "1") (pinfunction "1_1") (pintype "passive"))
      (node (ref "U3") (pin "20") (pinfunction "PIO[12]_20") (pintype "passive"))
    )
    (net (code "32") (name "/TX") (class "Default")
      (node (ref "R10") (pin "1") (pinfunction "1_1") (pintype "passive"))
      (node (ref "U3") (pin "19") (pinfunction "PIO[0]/UART_TX_19") (pintype "passive"))
    )
    (net (code "33") (name "/WP") (class "Default")
      (node (ref "R35") (pin "2") (pinfunction "2_2") (pintype "passive"))
      (node (ref "R36") (pin "2") (pinfunction "2_2") (pintype "passive"))
      (node (ref "U1") (pin "7") (pinfunction "WP_7") (pintype "passive"))
      (node (ref "U5") (pin "3") (pinfunction "nWP_3") (pintype "passive"))
    )
    (net (code "34") (name "AGND") (class "Default")
      (node (ref "C16") (pin "2") (pinfunction "2_2") (pintype "passive"))
      (node (ref "C19") (pin "2") (pinfunction "2_2") (pintype "passive"))
      (node (ref "C28") (pin "2") (pinfunction "2_2") (pintype "passive"))
      (node (ref "C31") (pin "1") (pinfunction "1_1") (pintype "passive"))
      (node (ref "C32") (pin "2") (pinfunction "2_2") (pintype "passive"))
      (node (ref "C33") (pin "2") (pinfunction "2_2") (pintype "passive"))
      (node (ref "C34") (pin "1") (pinfunction "1_1") (pintype "passive"))
      (node (ref "C35") (pin "2") (pinfunction "2_2") (pintype "passive"))
      (node (ref "C36") (pin "2") (pinfunction "2_2") (pintype "passive"))
      (node (ref "C37") (pin "2") (pinfunction "2_2") (pintype "passive"))
      (node (ref "C38") (pin "2") (pinfunction "2_2") (pintype "passive"))
      (node (ref "C41") (pin "2") (pinfunction "2_2") (pintype "passive"))
      (node (ref "C42") (pin "2") (pinfunction "2_2") (pintype "passive"))
      (node (ref "C43") (pin "2") (pinfunction "2_2") (pintype "passive"))
      (node (ref "C44") (pin "2") (pinfunction "2_2") (pintype "passive"))
      (node (ref "C45") (pin "2") (pinfunction "2_2") (pintype "passive"))
      (node (ref "C46") (pin "2") (pinfunction "2_2") (pintype "passive"))
      (node (ref "C47") (pin "2") (pinfunction "2_2") (pintype "passive"))
      (node (ref "C51") (pin "1") (pinfunction "1_1") (pintype "passive"))
      (node (ref "C52") (pin "2") (pinfunction "2_2") (pintype "passive"))
      (node (ref "ESD2") (pin "1") (pinfunction "1_1") (pintype "passive"))
      (node (ref "MIC1") (pin "2") (pinfunction "GND_2") (pintype "passive"))
      (node (ref "MIC1") (pin "3") (pinfunction "GND_3") (pintype "passive"))
      (node (ref "R20") (pin "2") (pinfunction "2_2") (pintype "passive"))
      (node (ref "R27") (pin "1") (pinfunction "1_1") (pintype "passive"))
      (node (ref "U2") (pin "13") (pinfunction "AGND_13") (pintype "passive"))
      (node (ref "U2") (pin "18") (pinfunction "AGND_18") (pintype "passive"))
      (node (ref "U2") (pin "29") (pinfunction "PAD_29") (pintype "passive"))
      (node (ref "U2") (pin "4") (pinfunction "DGND_4") (pintype "passive"))
      (node (ref "U2") (pin "6") (pinfunction "DGND_6") (pintype "passive"))
    )
    (net (code "35") (name "GND") (class "Default")
      (node (ref "ANT1") (pin "1") (pinfunction "A_1") (pintype "passive"))
      (node (ref "BAT-") (pin "1") (pinfunction "1_1") (pintype "passive"))
      (node (ref "C1") (pin "2") (pinfunction "2_2") (pintype "passive"))
      (node (ref "C10") (pin "2") (pinfunction "2_2") (pintype "passive"))
      (node (ref "C11") (pin "2") (pinfunction "2_2") (pintype "passive"))
      (node (ref "C12") (pin "2") (pinfunction "2_2") (pintype "passive"))
      (node (ref "C13") (pin "2") (pinfunction "2_2") (pintype "passive"))
      (node (ref "C14") (pin "2") (pinfunction "2_2") (pintype "passive"))
      (node (ref "C15") (pin "2") (pinfunction "2_2") (pintype "passive"))
      (node (ref "C17") (pin "2") (pinfunction "2_2") (pintype "passive"))
      (node (ref "C18") (pin "2") (pinfunction "2_2") (pintype "passive"))
      (node (ref "C2") (pin "2") (pinfunction "2_2") (pintype "passive"))
      (node (ref "C20") (pin "2") (pinfunction "2_2") (pintype "passive"))
      (node (ref "C21") (pin "2") (pinfunction "2_2") (pintype "passive"))
      (node (ref "C22") (pin "1") (pinfunction "1_1") (pintype "passive"))
      (node (ref "C24") (pin "1") (pinfunction "1_1") (pintype "passive"))
      (node (ref "C26") (pin "2") (pinfunction "2_2") (pintype "passive"))
      (node (ref "C27") (pin "2") (pinfunction "2_2") (pintype "passive"))
      (node (ref "C29") (pin "2") (pinfunction "2_2") (pintype "passive"))
      (node (ref "C3") (pin "2") (pinfunction "2_2") (pintype "passive"))
      (node (ref "C30") (pin "2") (pinfunction "2_2") (pintype "passive"))
      (node (ref "C39") (pin "2") (pinfunction "2_2") (pintype "passive"))
      (node (ref "C4") (pin "2") (pinfunction "2_2") (pintype "passive"))
      (node (ref "C40") (pin "2") (pinfunction "2_2") (pintype "passive"))
      (node (ref "C48") (pin "2") (pinfunction "2_2") (pintype "passive"))
      (node (ref "C49") (pin "2") (pinfunction "2_2") (pintype "passive"))
      (node (ref "C5") (pin "2") (pinfunction "2_2") (pintype "passive"))
      (node (ref "C50") (pin "2") (pinfunction "2_2") (pintype "passive"))
      (node (ref "C53") (pin "2") (pinfunction "2_2") (pintype "passive"))
      (node (ref "C6") (pin "2") (pinfunction "2_2") (pintype "passive"))
      (node (ref "C7") (pin "2") (pinfunction "2_2") (pintype "passive"))
      (node (ref "C8") (pin "2") (pinfunction "2_2") (pintype "passive"))
      (node (ref "C9") (pin "2") (pinfunction "2_2") (pintype "passive"))
      (node (ref "ESD1") (pin "2") (pinfunction "2_2") (pintype "passive"))
      (node (ref "ESD2") (pin "2") (pinfunction "2_2") (pintype "passive"))
      (node (ref "ESD3") (pin "2") (pinfunction "2_2") (pintype "passive"))
      (node (ref "J1") (pin "1") (pinfunction "1_1") (pintype "passive"))
      (node (ref "PAD1") (pin "1") (pinfunction "1_1") (pintype "passive"))
      (node (ref "Q1") (pin "2") (pinfunction "2_2") (pintype "passive"))
      (node (ref "Q2") (pin "2") (pinfunction "2_2") (pintype "input"))
      (node (ref "R15") (pin "2") (pinfunction "2_2") (pintype "passive"))
      (node (ref "R27") (pin "2") (pinfunction "2_2") (pintype "passive"))
      (node (ref "R35") (pin "1") (pinfunction "1_1") (pintype "passive"))
      (node (ref "R4") (pin "1") (pinfunction "1_1") (pintype "passive"))
      (node (ref "U1") (pin "1") (pinfunction "A0_1") (pintype "passive"))
      (node (ref "U1") (pin "2") (pinfunction "A1_2") (pintype "passive"))
      (node (ref "U1") (pin "3") (pinfunction "A2_3") (pintype "passive"))
      (node (ref "U1") (pin "4") (pinfunction "GND_4") (pintype "passive"))
      (node (ref "U3") (pin "0") (pinfunction "GND_0") (pintype "passive"))
      (node (ref "U3") (pin "11") (pinfunction "N/C_11") (pintype "passive"))
      (node (ref "U3") (pin "12") (pinfunction "N/C_12") (pintype "passive"))
      (node (ref "U3") (pin "9") (pinfunction "N/C_9") (pintype "passive"))
      (node (ref "U4") (pin "1") (pinfunction "SDO_1") (pintype "passive"))
      (node (ref "U4") (pin "6") (pinfunction "GNDIO_6") (pintype "passive"))
      (node (ref "U4") (pin "7") (pinfunction "GND_7") (pintype "passive"))
      (node (ref "U5") (pin "4") (pinfunction "GND_4") (pintype "passive"))
      (node (ref "Y2") (pin "3") (pinfunction "2_3") (pintype "passive"))
    )
    (net (code "36") (name "Net-(ANT1-Pad2)") (class "Default")
      (node (ref "ANT1") (pin "2") (pinfunction "2_2") (pintype "passive"))
      (node (ref "C11") (pin "1") (pinfunction "1_1") (pintype "passive"))
      (node (ref "L4") (pin "1") (pinfunction "1_1") (pintype "passive"))
      (node (ref "PAD2") (pin "1") (pinfunction "1_1") (pintype "passive"))
    )
    (net (code "37") (name "Net-(BAT+-Pad1)") (class "Default")
      (node (ref "BAT+") (pin "1") (pinfunction "1_1") (pintype "passive"))
      (node (ref "Q2") (pin "3") (pinfunction "3_3") (pintype "input"))
    )
    (net (code "38") (name "Net-(C3-Pad1)") (class "Default")
      (node (ref "C3") (pin "1") (pinfunction "1_1") (pintype "passive"))
      (node (ref "C4") (pin "1") (pinfunction "1_1") (pintype "passive"))
      (node (ref "U3") (pin "55") (pinfunction "VDD_CORE_55") (pintype "passive"))
      (node (ref "U3") (pin "7") (pinfunction "VDD_CORE_7") (pintype "passive"))
    )
    (net (code "39") (name "Net-(C29-Pad1)") (class "Default")
      (node (ref "C29") (pin "1") (pinfunction "1_1") (pintype "passive"))
      (node (ref "R28") (pin "2") (pinfunction "2_2") (pintype "passive"))
      (node (ref "S1") (pin "2") (pinfunction "2_2") (pintype "passive"))
      (node (ref "S2") (pin "2") (pinfunction "2_2") (pintype "passive"))
      (node (ref "S3") (pin "2") (pinfunction "2_2") (pintype "passive"))
      (node (ref "S4") (pin "2") (pinfunction "2_2") (pintype "passive"))
      (node (ref "S5") (pin "2") (pinfunction "2_2") (pintype "passive"))
      (node (ref "S6") (pin "2") (pinfunction "2_2") (pintype "passive"))
      (node (ref "S7") (pin "2") (pinfunction "2_2") (pintype "passive"))
    )
    (net (code "40") (name "Net-(C30-Pad1)") (class "Default")
      (node (ref "C30") (pin "1") (pinfunction "1_1") (pintype "passive"))
      (node (ref "R29") (pin "2") (pinfunction "2_2") (pintype "passive"))
      (node (ref "S10") (pin "2") (pinfunction "2_2") (pintype "passive"))
      (node (ref "S11") (pin "2") (pinfunction "2_2") (pintype "passive"))
      (node (ref "S12") (pin "2") (pinfunction "2_2") (pintype "passive"))
      (node (ref "S13") (pin "2") (pinfunction "2_2") (pintype "passive"))
      (node (ref "S14") (pin "2") (pinfunction "2_2") (pintype "passive"))
      (node (ref "S8") (pin "2") (pinfunction "2_2") (pintype "passive"))
      (node (ref "S9") (pin "2") (pinfunction "2_2") (pintype "passive"))
    )
    (net (code "41") (name "Net-(C39-Pad1)") (class "Default")
      (node (ref "C39") (pin "1") (pinfunction "1_1") (pintype "passive"))
      (node (ref "R5") (pin "2") (pinfunction "2_2") (pintype "passive"))
      (node (ref "S15") (pin "2") (pinfunction "2_2") (pintype "passive"))
      (node (ref "S16") (pin "2") (pinfunction "2_2") (pintype "passive"))
      (node (ref "S17") (pin "2") (pinfunction "2_2") (pintype "passive"))
      (node (ref "S18") (pin "2") (pinfunction "2_2") (pintype "passive"))
      (node (ref "S19") (pin "2") (pinfunction "2_2") (pintype "passive"))
      (node (ref "S20") (pin "2") (pinfunction "2_2") (pintype "passive"))
      (node (ref "S21") (pin "2") (pinfunction "2_2") (pintype "passive"))
    )
    (net (code "42") (name "Net-(J1-Pad2)") (class "Default")
      (node (ref "J1") (pin "2") (pinfunction "2_2") (pintype "passive"))
      (node (ref "R7") (pin "1") (pinfunction "1_1") (pintype "passive"))
    )
    (net (code "43") (name "Net-(J1-Pad3)") (class "Default")
      (node (ref "J1") (pin "3") (pinfunction "3_3") (pintype "passive"))
      (node (ref "R9") (pin "1") (pinfunction "1_1") (pintype "passive"))
    )
    (net (code "44") (name "Net-(J1-Pad4)") (class "Default")
      (node (ref "J1") (pin "4") (pinfunction "4_4") (pintype "passive"))
      (node (ref "R11") (pin "1") (pinfunction "1_1") (pintype "passive"))
    )
    (net (code "45") (name "Net-(J1-Pad5)") (class "Default")
      (node (ref "J1") (pin "5") (pinfunction "5_5") (pintype "passive"))
      (node (ref "R13") (pin "1") (pinfunction "1_1") (pintype "passive"))
    )
    (net (code "46") (name "Net-(J1-Pad6)") (class "Default")
      (node (ref "J1") (pin "6") (pinfunction "6_6") (pintype "passive"))
      (node (ref "R14") (pin "1") (pinfunction "1_1") (pintype "passive"))
    )
    (net (code "47") (name "Net-(L3-Pad2)") (class "Default")
      (node (ref "L3") (pin "2") (pintype "passive"))
      (node (ref "Q2") (pin "1") (pinfunction "1_1") (pintype "input"))
    )
    (net (code "48") (name "Net-(LD1-Pad1)") (class "Default")
      (node (ref "LD1") (pin "1") (pinfunction "1_1") (pintype "passive"))
      (node (ref "R1") (pin "1") (pinfunction "1_1") (pintype "passive"))
    )
    (net (code "49") (name "Net-(LD1-Pad2)") (class "Default")
      (node (ref "LD1") (pin "2") (pinfunction "2_2") (pintype "passive"))
      (node (ref "Q1") (pin "3") (pinfunction "3_3") (pintype "passive"))
    )
    (net (code "50") (name "Net-(MIC1-OUT)") (class "Default")
      (node (ref "C25") (pin "1") (pinfunction "1_1") (pintype "passive"))
      (node (ref "C36") (pin "1") (pinfunction "1_1") (pintype "passive"))
      (node (ref "ESD1") (pin "1") (pinfunction "1_1") (pintype "passive"))
      (node (ref "MIC1") (pin "4") (pinfunction "OUT_4") (pintype "passive"))
    )
    (net (code "51") (name "Net-(MIC1-VDD)") (class "Default")
      (node (ref "C28") (pin "1") (pinfunction "1_1") (pintype "passive"))
      (node (ref "C35") (pin "1") (pinfunction "1_1") (pintype "passive"))
      (node (ref "ESD3") (pin "1") (pinfunction "1_1") (pintype "passive"))
      (node (ref "L5") (pin "2") (pinfunction "2_2") (pintype "passive"))
      (node (ref "MIC1") (pin "1") (pinfunction "VDD_1") (pintype "passive"))
    )
    (net (code "52") (name "Net-(Q1-Pad1)") (class "Default")
      (node (ref "Q1") (pin "1") (pinfunction "1_1") (pintype "passive"))
      (node (ref "R37") (pin "1") (pinfunction "1_1") (pintype "passive"))
    )
    (net (code "53") (name "Net-(R6-Pad1)") (class "Default")
      (node (ref "R6") (pin "1") (pinfunction "1_1") (pintype "passive"))
      (node (ref "SDA") (pin "1") (pinfunction "1_1") (pintype "passive"))
    )
    (net (code "54") (name "Net-(R8-Pad1)") (class "Default")
      (node (ref "R8") (pin "1") (pinfunction "1_1") (pintype "passive"))
      (node (ref "SCL") (pin "1") (pinfunction "1_1") (pintype "passive"))
    )
    (net (code "55") (name "Net-(R10-Pad2)") (class "Default")
      (node (ref "R10") (pin "2") (pinfunction "2_2") (pintype "passive"))
      (node (ref "TX") (pin "1") (pinfunction "1_1") (pintype "passive"))
    )
    (net (code "56") (name "Net-(R12-Pad2)") (class "Default")
      (node (ref "R12") (pin "2") (pinfunction "2_2") (pintype "passive"))
      (node (ref "RX") (pin "1") (pinfunction "1_1") (pintype "passive"))
    )
    (net (code "57") (name "Net-(SENSOR_INT2-99)") (class "Default")
      (node (ref "R33") (pin "1") (pinfunction "1_1") (pintype "passive"))
      (node (ref "SENSOR_INT2") (pin "1") (pinfunction "99_1") (pintype "passive"))
    )
    (net (code "58") (name "Net-(U1-VCC)") (class "Default")
      (node (ref "C10") (pin "1") (pinfunction "1_1") (pintype "passive"))
      (node (ref "R36") (pin "1") (pinfunction "1_1") (pintype "passive"))
      (node (ref "R38") (pin "1") (pinfunction "1_1") (pintype "passive"))
      (node (ref "U1") (pin "8") (pinfunction "VCC_8") (pintype "passive"))
      (node (ref "U3") (pin "52") (pinfunction "PIO[2]_52") (pintype "passive"))
    )
    (net (code "59") (name "Net-(U2-ADCVREF)") (class "Default")
      (node (ref "C41") (pin "1") (pinfunction "1_1") (pintype "passive"))
      (node (ref "C42") (pin "1") (pinfunction "1_1") (pintype "passive"))
      (node (ref "U2") (pin "19") (pinfunction "ADCVREF_19") (pintype "passive"))
    )
    (net (code "60") (name "Net-(U2-ASDOUT)") (class "Default")
      (node (ref "C47") (pin "1") (pinfunction "1_1") (pintype "passive"))
      (node (ref "R26") (pin "1") (pinfunction "1_1") (pintype "passive"))
      (node (ref "U2") (pin "8") (pinfunction "ASDOUT_8") (pintype "passive"))
    )
    (net (code "61") (name "Net-(U2-CCLK)") (class "Default")
      (node (ref "R19") (pin "1") (pinfunction "1_1") (pintype "passive"))
      (node (ref "U2") (pin "28") (pinfunction "CCLK_28") (pintype "passive"))
    )
    (net (code "62") (name "Net-(U2-CDATA)") (class "Default")
      (node (ref "R18") (pin "1") (pinfunction "1_1") (pintype "passive"))
      (node (ref "U2") (pin "27") (pinfunction "CDATA_27") (pintype "passive"))
    )
    (net (code "63") (name "Net-(U2-CE)") (class "Default")
      (node (ref "R20") (pin "1") (pinfunction "1_1") (pintype "passive"))
      (node (ref "U2") (pin "26") (pinfunction "CE_26") (pintype "passive"))
    )
    (net (code "64") (name "Net-(U2-LIN2)") (class "Default")
      (node (ref "C25") (pin "2") (pinfunction "2_2") (pintype "passive"))
      (node (ref "C51") (pin "2") (pinfunction "2_2") (pintype "passive"))
      (node (ref "U2") (pin "22") (pinfunction "LIN2_22") (pintype "passive"))
    )
    (net (code "65") (name "Net-(U2-LRCK)") (class "Default")
      (node (ref "C46") (pin "1") (pinfunction "1_1") (pintype "passive"))
      (node (ref "R25") (pin "1") (pinfunction "1_1") (pintype "passive"))
      (node (ref "U2") (pin "7") (pinfunction "LRCK_7") (pintype "passive"))
    )
    (net (code "66") (name "Net-(U2-MCLK)") (class "Default")
      (node (ref "C34") (pin "2") (pinfunction "2_2") (pintype "passive"))
      (node (ref "R22") (pin "1") (pinfunction "1_1") (pintype "passive"))
      (node (ref "U2") (pin "1") (pinfunction "MCLK_1") (pintype "passive"))
    )
    (net (code "67") (name "Net-(U2-MICBIAS)") (class "Default")
      (node (ref "C16") (pin "1") (pinfunction "1_1") (pintype "passive"))
      (node (ref "C19") (pin "1") (pinfunction "1_1") (pintype "passive"))
      (node (ref "L5") (pin "1") (pinfunction "1_1") (pintype "passive"))
      (node (ref "U2") (pin "25") (pinfunction "MICBIAS_25") (pintype "passive"))
    )
    (net (code "68") (name "Net-(U2-RIN2)") (class "Default")
      (node (ref "C31") (pin "2") (pinfunction "2_2") (pintype "passive"))
      (node (ref "C52") (pin "1") (pinfunction "1_1") (pintype "passive"))
      (node (ref "U2") (pin "21") (pinfunction "RIN2_21") (pintype "passive"))
    )
    (net (code "69") (name "Net-(U2-SCLK)") (class "Default")
      (node (ref "C45") (pin "1") (pinfunction "1_1") (pintype "passive"))
      (node (ref "R24") (pin "1") (pinfunction "1_1") (pintype "passive"))
      (node (ref "U2") (pin "5") (pinfunction "SCLK_5") (pintype "passive"))
    )
    (net (code "70") (name "Net-(U2-VMID)") (class "Default")
      (node (ref "C37") (pin "1") (pinfunction "1_1") (pintype "passive"))
      (node (ref "C38") (pin "1") (pinfunction "1_1") (pintype "passive"))
      (node (ref "U2") (pin "20") (pinfunction "VMID_20") (pintype "passive"))
    )
    (net (code "71") (name "Net-(U3-PIO[9])") (class "Default")
      (node (ref "R37") (pin "2") (pinfunction "2_2") (pintype "passive"))
      (node (ref "U3") (pin "42") (pinfunction "PIO[9]_42") (pintype "passive"))
    )
    (net (code "72") (name "Net-(U3-RF)") (class "Default")
      (node (ref "C12") (pin "1") (pinfunction "1_1") (pintype "passive"))
      (node (ref "C13") (pin "1") (pinfunction "1_1") (pintype "passive"))
      (node (ref "L4") (pin "2") (pinfunction "2_2") (pintype "passive"))
      (node (ref "U3") (pin "10") (pinfunction "RF_10") (pintype "passive"))
    )
    (net (code "73") (name "Net-(U3-SMPS_LX)") (class "Default")
      (node (ref "L2") (pin "1") (pinfunction "1_1") (pintype "passive"))
      (node (ref "U3") (pin "56") (pinfunction "SMPS_LX_56") (pintype "passive"))
    )
    (net (code "74") (name "Net-(U3-VDD_BAT{slash}VREGENABLE)") (class "Default")
      (node (ref "C7") (pin "1") (pinfunction "1_1") (pintype "passive"))
      (node (ref "L1") (pin "2") (pinfunction "2_2") (pintype "passive"))
      (node (ref "U3") (pin "3") (pinfunction "VDD_BAT/VREGENABLE_3") (pintype "passive"))
    )
    (net (code "75") (name "Net-(U3-VDD_REG_IN)") (class "Default")
      (node (ref "C1") (pin "1") (pinfunction "1_1") (pintype "passive"))
      (node (ref "C2") (pin "1") (pinfunction "1_1") (pintype "passive"))
      (node (ref "L2") (pin "2") (pinfunction "2_2") (pintype "passive"))
      (node (ref "U3") (pin "8") (pinfunction "VDD_REG_IN_8") (pintype "passive"))
    )
    (net (code "76") (name "Net-(U3-VDD_XTAL)") (class "Default")
      (node (ref "C14") (pin "1") (pinfunction "1_1") (pintype "passive"))
      (node (ref "U3") (pin "13") (pinfunction "VDD_XTAL_13") (pintype "passive"))
    )
    (net (code "77") (name "Net-(U3-WAKE)") (class "Default")
      (node (ref "R4") (pin "2") (pinfunction "2_2") (pintype "passive"))
      (node (ref "U3") (pin "6") (pinfunction "WAKE_6") (pintype "passive"))
    )
    (net (code "78") (name "Net-(U3-XTAL_16M_IN)") (class "Default")
      (node (ref "C21") (pin "1") (pinfunction "1_1") (pintype "passive"))
      (node (ref "U3") (pin "15") (pinfunction "XTAL_16M_IN_15") (pintype "passive"))
      (node (ref "Y2") (pin "2") (pinfunction "3_2") (pintype "passive"))
    )
    (net (code "79") (name "Net-(U3-XTAL_16M_OUT)") (class "Default")
      (node (ref "C20") (pin "1") (pinfunction "1_1") (pintype "passive"))
      (node (ref "U3") (pin "14") (pinfunction "XTAL_16M_OUT_14") (pintype "passive"))
      (node (ref "Y2") (pin "1") (pinfunction "1_1") (pintype "passive"))
    )
    (net (code "80") (name "Net-(U3-XTAL_32K_IN)") (class "Default")
      (node (ref "C18") (pin "1") (pinfunction "1_1") (pintype "passive"))
      (node (ref "U3") (pin "5") (pinfunction "XTAL_32K_IN_5") (pintype "passive"))
      (node (ref "Y1") (pin "2") (pinfunction "2_2") (pintype "passive"))
    )
    (net (code "81") (name "Net-(U3-XTAL_32K_OUT)") (class "Default")
      (node (ref "C17") (pin "1") (pinfunction "1_1") (pintype "passive"))
      (node (ref "U3") (pin "4") (pinfunction "XTAL_32K_OUT_4") (pintype "passive"))
      (node (ref "Y1") (pin "1") (pinfunction "1_1") (pintype "passive"))
    )
    (net (code "82") (name "Net-(U4-INT1)") (class "Default")
      (node (ref "R16") (pin "2") (pinfunction "2_2") (pintype "passive"))
      (node (ref "R33") (pin "2") (pinfunction "2_2") (pintype "passive"))
      (node (ref "U4") (pin "4") (pinfunction "INT1_4") (pintype "passive"))
    )
    (net (code "83") (name "Net-(U4-OSDO)") (class "Default")
      (node (ref "C53") (pin "1") (pinfunction "1_1") (pintype "passive"))
      (node (ref "U4") (pin "11") (pinfunction "OSDO_11") (pintype "passive"))
    )
    (net (code "84") (name "Net-(U4-SCX)") (class "Default")
      (node (ref "R30") (pin "1") (pinfunction "1_1") (pintype "passive"))
      (node (ref "U4") (pin "13") (pinfunction "SCX_13") (pintype "passive"))
    )
    (net (code "85") (name "Net-(U4-SDX)") (class "Default")
      (node (ref "R31") (pin "1") (pinfunction "1_1") (pintype "passive"))
      (node (ref "U4") (pin "14") (pinfunction "SDX_14") (pintype "passive"))
    )
    (net (code "86") (name "Net-(U5-VCC)") (class "Default")
      (node (ref "C50") (pin "1") (pinfunction "1_1") (pintype "passive"))
      (node (ref "R38") (pin "2") (pinfunction "2_2") (pintype "passive"))
      (node (ref "R39") (pin "1") (pinfunction "1_1") (pintype "passive"))
      (node (ref "U5") (pin "7") (pinfunction "nHOLD_7") (pintype "passive"))
      (node (ref "U5") (pin "8") (pinfunction "VCC_8") (pintype "passive"))
    )
    (net (code "87") (name "VBAT") (class "Default")
      (node (ref "C15") (pin "1") (pinfunction "1_1") (pintype "passive"))
      (node (ref "C27") (pin "1") (pinfunction "1_1") (pintype "passive"))
      (node (ref "C32") (pin "1") (pinfunction "1_1") (pintype "passive"))
      (node (ref "C33") (pin "1") (pinfunction "1_1") (pintype "passive"))
      (node (ref "C43") (pin "1") (pinfunction "1_1") (pintype "passive"))
      (node (ref "C44") (pin "1") (pinfunction "1_1") (pintype "passive"))
      (node (ref "C48") (pin "1") (pinfunction "1_1") (pintype "passive"))
      (node (ref "C49") (pin "1") (pinfunction "1_1") (pintype "passive"))
      (node (ref "C5") (pin "1") (pinfunction "1_1") (pintype "passive"))
      (node (ref "C6") (pin "1") (pinfunction "1_1") (pintype "passive"))
      (node (ref "C8") (pin "1") (pinfunction "1_1") (pintype "passive"))
      (node (ref "C9") (pin "1") (pinfunction "1_1") (pintype "passive"))
      (node (ref "L1") (pin "1") (pinfunction "1_1") (pintype "passive"))
      (node (ref "L3") (pin "1") (pintype "passive"))
      (node (ref "R1") (pin "2") (pinfunction "2_2") (pintype "passive"))
      (node (ref "R2") (pin "1") (pinfunction "1_1") (pintype "passive"))
      (node (ref "R3") (pin "1") (pinfunction "1_1") (pintype "passive"))
      (node (ref "R32") (pin "2") (pinfunction "2_2") (pintype "passive"))
      (node (ref "R39") (pin "2") (pinfunction "2_2") (pintype "passive"))
      (node (ref "U2") (pin "17") (pinfunction "AVDD_17") (pintype "passive"))
      (node (ref "U2") (pin "2") (pinfunction "DVDD_2") (pintype "passive"))
      (node (ref "U2") (pin "3") (pinfunction "PVDD_3") (pintype "passive"))
      (node (ref "U3") (pin "1") (pinfunction "VDD_BAT_SMPS_1") (pintype "passive"))
      (node (ref "U3") (pin "36") (pinfunction "VDD_PADS_36") (pintype "passive"))
    )
    (net (code "88") (name "VDD_SENSOR") (class "Default")
      (node (ref "C26") (pin "1") (pinfunction "1_1") (pintype "passive"))
      (node (ref "C40") (pin "1") (pinfunction "1_1") (pintype "passive"))
      (node (ref "R32") (pin "1") (pinfunction "1_1") (pintype "passive"))
      (node (ref "U4") (pin "12") (pinfunction "CSB_12") (pintype "passive"))
      (node (ref "U4") (pin "5") (pinfunction "VDDIO_5") (pintype "passive"))
      (node (ref "U4") (pin "8") (pinfunction "VDD_8") (pintype "passive"))
    )
    (net (code "89") (name "unconnected-(U2-DMIC_SCL-Pad9)") (class "Default")
      (node (ref "U2") (pin "9") (pinfunction "DMIC_SCL_9") (pintype "passive+no_connect"))
    )
    (net (code "90") (name "unconnected-(U2-LIN1-Pad24)") (class "Default")
      (node (ref "U2") (pin "24") (pinfunction "LIN1_24") (pintype "passive+no_connect"))
    )
    (net (code "91") (name "unconnected-(U2-NC-Pad10)") (class "Default")
      (node (ref "U2") (pin "10") (pinfunction "NC_10") (pintype "passive+no_connect"))
    )
    (net (code "92") (name "unconnected-(U2-NC-Pad11)") (class "Default")
      (node (ref "U2") (pin "11") (pinfunction "NC_11") (pintype "passive+no_connect"))
    )
    (net (code "93") (name "unconnected-(U2-NC-Pad12)") (class "Default")
      (node (ref "U2") (pin "12") (pinfunction "NC_12") (pintype "passive+no_connect"))
    )
    (net (code "94") (name "unconnected-(U2-NC-Pad14)") (class "Default")
      (node (ref "U2") (pin "14") (pinfunction "NC_14") (pintype "passive+no_connect"))
    )
    (net (code "95") (name "unconnected-(U2-NC-Pad15)") (class "Default")
      (node (ref "U2") (pin "15") (pinfunction "NC_15") (pintype "passive+no_connect"))
    )
    (net (code "96") (name "unconnected-(U2-NC-Pad16)") (class "Default")
      (node (ref "U2") (pin "16") (pinfunction "NC_16") (pintype "passive+no_connect"))
    )
    (net (code "97") (name "unconnected-(U2-RIN1-Pad23)") (class "Default")
      (node (ref "U2") (pin "23") (pinfunction "RIN1_23") (pintype "passive+no_connect"))
    )
    (net (code "98") (name "unconnected-(U3-AIO[0]-Pad18)") (class "Default")
      (node (ref "U3") (pin "18") (pinfunction "AIO[0]_18") (pintype "passive+no_connect"))
    )
    (net (code "99") (name "unconnected-(U3-AIO[1]-Pad17)") (class "Default")
      (node (ref "U3") (pin "17") (pinfunction "AIO[1]_17") (pintype "passive+no_connect"))
    )
    (net (code "100") (name "unconnected-(U3-AIO[2]-Pad16)") (class "Default")
      (node (ref "U3") (pin "16") (pinfunction "AIO[2]_16") (pintype "passive+no_connect"))
    )
    (net (code "101") (name "unconnected-(U3-N{slash}C-Pad2)") (class "Default")
      (node (ref "U3") (pin "2") (pinfunction "N/C_2") (pintype "passive+no_connect"))
    )
    (net (code "102") (name "unconnected-(U3-PIO[19]-Pad32)") (class "Default")
      (node (ref "U3") (pin "32") (pinfunction "PIO[19]_32") (pintype "passive+no_connect"))
    )
    (net (code "103") (name "unconnected-(U3-PIO[20]-Pad33)") (class "Default")
      (node (ref "U3") (pin "33") (pinfunction "PIO[20]_33") (pintype "passive+no_connect"))
    )
    (net (code "104") (name "unconnected-(U3-PIO[31]-Pad51)") (class "Default")
      (node (ref "U3") (pin "51") (pinfunction "PIO[31]_51") (pintype "passive+no_connect"))
    )
    (net (code "105") (name "unconnected-(U4-ASCX-Pad3)") (class "Default")
      (node (ref "U4") (pin "3") (pinfunction "ASCX_3") (pintype "passive+no_connect"))
    )
    (net (code "106") (name "unconnected-(U4-ASDX-Pad2)") (class "Default")
      (node (ref "U4") (pin "2") (pinfunction "ASDX_2") (pintype "passive+no_connect"))
    )
    (net (code "107") (name "unconnected-(U4-INT2-Pad9)") (class "Default")
      (node (ref "U4") (pin "9") (pinfunction "INT2_9") (pintype "passive+no_connect"))
    )
    (net (code "108") (name "unconnected-(U4-OSCB-Pad10)") (class "Default")
      (node (ref "U4") (pin "10") (pinfunction "OSCB_10") (pintype "passive+no_connect"))
    )
  )
)
